# tyrmt.net
KiCad netlist of a schematic drawn in EAGLE
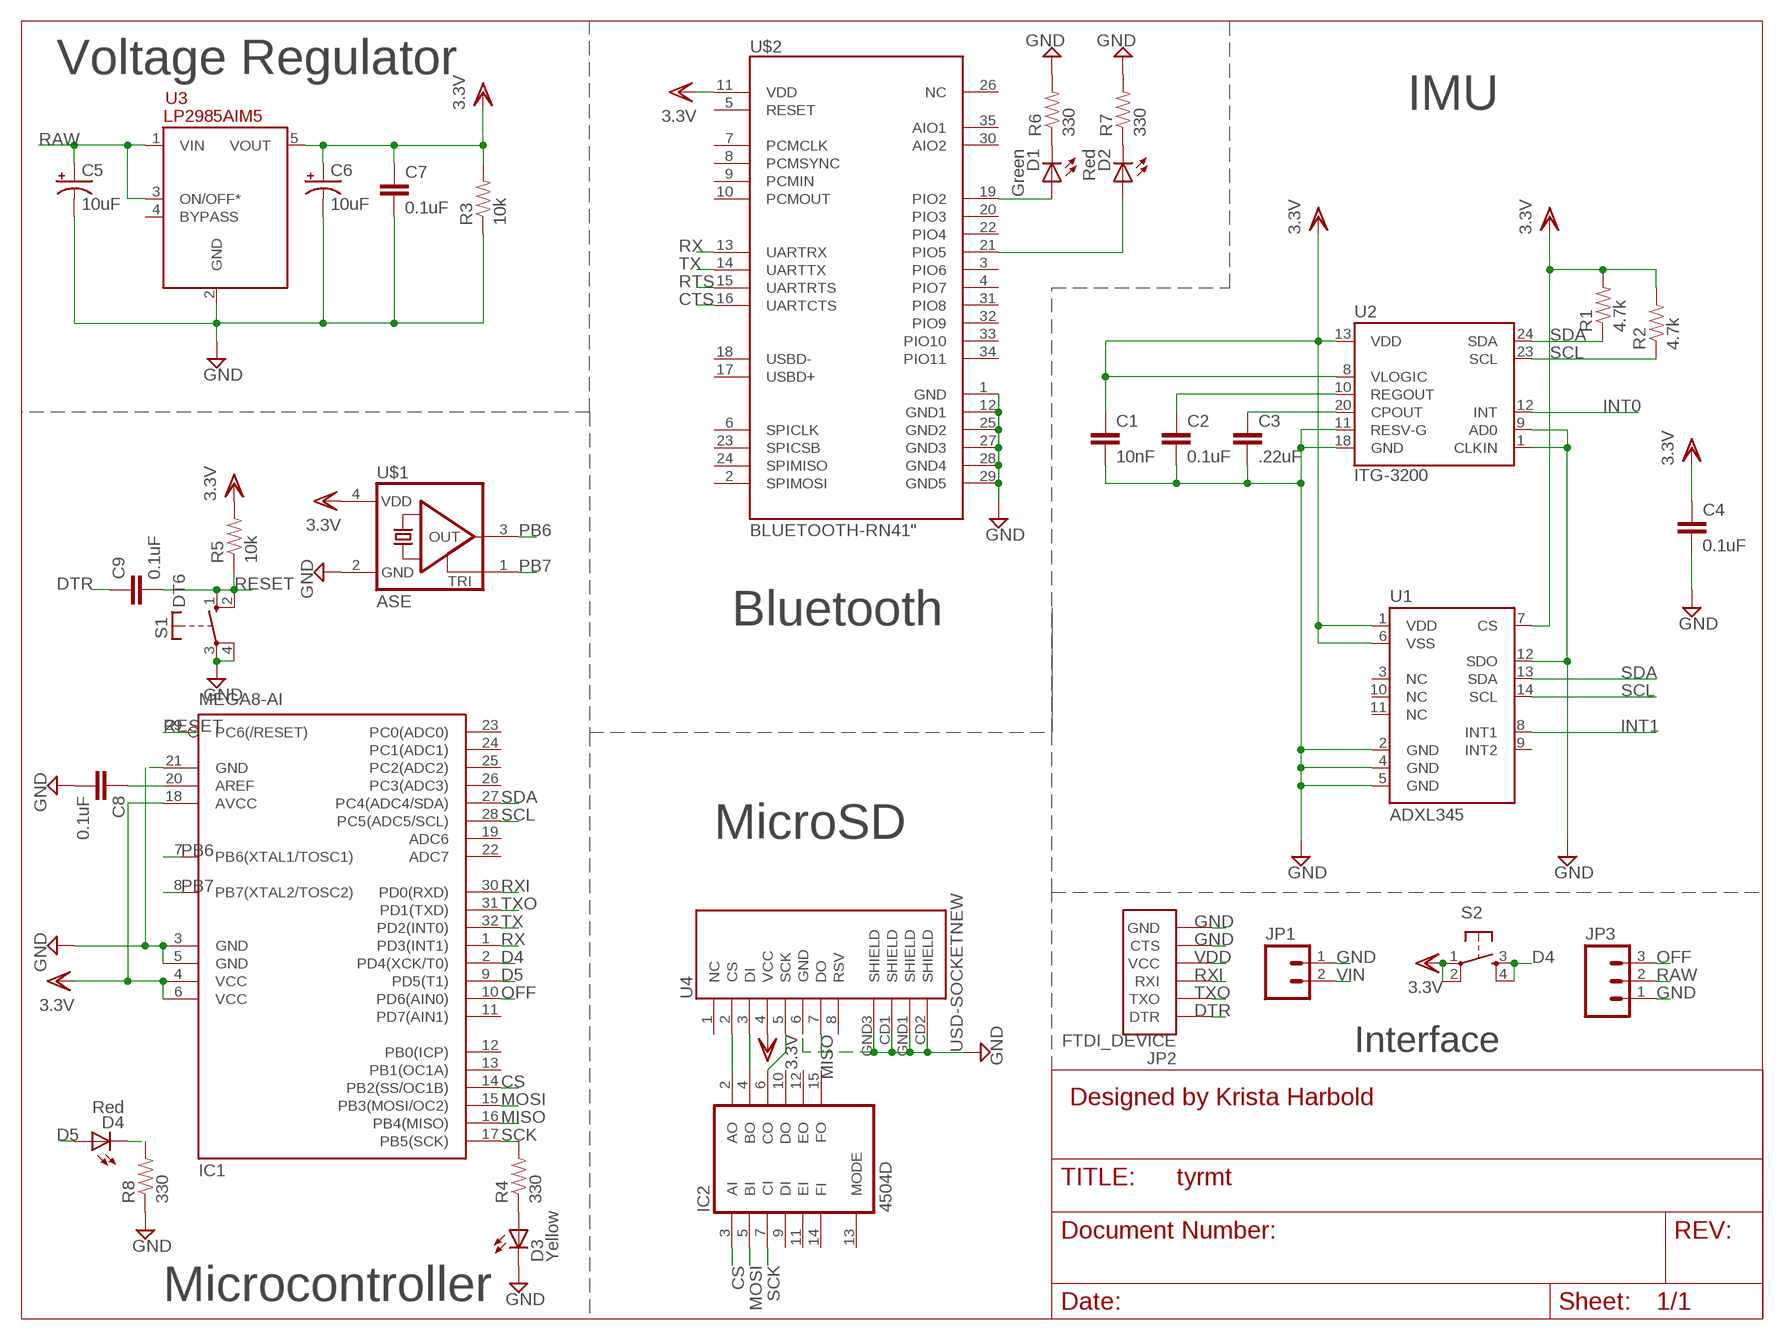
[diagram p0: schematic, sheet 1]

(export (version "E")
  (design (tool "Eeschema 10.0.6"))
  (components
    (comp (ref "C1")
      (value "10nF")
      (footprint "eagle-import:0402-CAP")
      (libsource (lib "eagle-import") (part "10NF-CER"))
    )
    (comp (ref "C2")
      (value "0.1uF")
      (footprint "eagle-import:0402-CAP")
      (libsource (lib "eagle-import") (part ".1UF-CER"))
    )
    (comp (ref "C3")
      (value ".22uF")
      (footprint "eagle-import:0402-CAP")
      (libsource (lib "eagle-import") (part ".22UF-CER"))
    )
    (comp (ref "C4")
      (value "0.1uF")
      (footprint "eagle-import:0402-CAP")
      (libsource (lib "eagle-import") (part ".1UF-CER"))
    )
    (comp (ref "C5")
      (value "10uF")
      (footprint "eagle-import:EIA3216")
      (libsource (lib "eagle-import") (part "10UF-16V-10%(TANT)"))
    )
    (comp (ref "C6")
      (value "10uF")
      (footprint "eagle-import:EIA3216")
      (libsource (lib "eagle-import") (part "10UF-16V-10%(TANT)"))
    )
    (comp (ref "C7")
      (value "0.1uF")
      (footprint "eagle-import:0402-CAP")
      (libsource (lib "eagle-import") (part ".1UF-CER"))
    )
    (comp (ref "C8")
      (value "0.1uF")
      (footprint "eagle-import:0402-CAP")
      (libsource (lib "eagle-import") (part ".1UF-CER"))
    )
    (comp (ref "C9")
      (value "0.1uF")
      (footprint "eagle-import:0402-CAP")
      (libsource (lib "eagle-import") (part ".1UF-CER"))
    )
    (comp (ref "D1")
      (value "Green")
      (footprint "eagle-import:SFH482")
      (libsource (lib "eagle-import") (part "SFH482"))
    )
    (comp (ref "D2")
      (value "Red")
      (footprint "eagle-import:SFH482")
      (libsource (lib "eagle-import") (part "SFH482"))
    )
    (comp (ref "D3")
      (value "Yellow")
      (footprint "eagle-import:SFH482")
      (libsource (lib "eagle-import") (part "SFH482"))
    )
    (comp (ref "D4")
      (value "Red")
      (footprint "eagle-import:SFH482")
      (libsource (lib "eagle-import") (part "SFH482"))
    )
    (comp (ref "IC1")
      (value "MEGA8-AI")
      (footprint "eagle-import:TQFP32-08")
      (fields (field (name "MPN") "ATMEGA8-16AU"))
      (libsource (lib "eagle-import") (part "MEGA8-AI"))
    )
    (comp (ref "IC2")
      (value "4504D")
      (footprint "eagle-import:SO16")
      (libsource (lib "eagle-import") (part "4504D"))
    )
    (comp (ref "JP1")
      (value "M02-JST-2MM-SMT")
      (footprint "eagle-import:JST-2-SMD")
      (libsource (lib "eagle-import") (part "M02-JST-2MM-SMT"))
    )
    (comp (ref "JP2")
      (value "FTDI_DEVICE")
      (footprint "eagle-import:FTDI_DEVICE_SIDE")
      (libsource (lib "eagle-import") (part "FTDI_DEVICE"))
    )
    (comp (ref "JP3")
      (value "M03POLAR")
      (footprint "eagle-import:MOLEX-1X3")
      (libsource (lib "eagle-import") (part "M03POLAR"))
    )
    (comp (ref "R1")
      (value "4.7k")
      (footprint "eagle-import:0402-RES")
      (libsource (lib "eagle-import") (part "RESISTOR0402-RES"))
    )
    (comp (ref "R2")
      (value "4.7k")
      (footprint "eagle-import:0402-RES")
      (libsource (lib "eagle-import") (part "RESISTOR0402-RES"))
    )
    (comp (ref "R3")
      (value "10k")
      (footprint "eagle-import:0402-RES")
      (libsource (lib "eagle-import") (part "RESISTOR0402-RES"))
    )
    (comp (ref "R4")
      (value "330")
      (footprint "eagle-import:0402-RES")
      (libsource (lib "eagle-import") (part "RESISTOR0402-RES"))
    )
    (comp (ref "R5")
      (value "10k")
      (footprint "eagle-import:0402-RES")
      (libsource (lib "eagle-import") (part "RESISTOR0402-RES"))
    )
    (comp (ref "R6")
      (value "330")
      (footprint "eagle-import:0402-RES")
      (libsource (lib "eagle-import") (part "RESISTOR0402-RES"))
    )
    (comp (ref "R7")
      (value "330")
      (footprint "eagle-import:0402-RES")
      (libsource (lib "eagle-import") (part "RESISTOR0402-RES"))
    )
    (comp (ref "R8")
      (value "330")
      (footprint "eagle-import:0402-RES")
      (libsource (lib "eagle-import") (part "RESISTOR0402-RES"))
    )
    (comp (ref "S1")
      (value "DT6")
      (footprint "eagle-import:DT6")
      (libsource (lib "eagle-import") (part "DT6"))
    )
    (comp (ref "S2")
      (value "TAC_SWITCHSMD")
      (footprint "eagle-import:TACTILE_SWITCH_SMD")
      (libsource (lib "eagle-import") (part "TAC_SWITCHSMD"))
    )
    (comp (ref "U$1")
      (value "ASE")
      (footprint "eagle-import:ASE")
      (libsource (lib "eagle-import") (part "ASE"))
    )
    (comp (ref "U$2")
      (value "BLUETOOTH-RN41\"")
      (footprint "eagle-import:RN41")
      (libsource (lib "eagle-import") (part "BLUETOOTH-RN41{dblquote}"))
    )
    (comp (ref "U1")
      (value "ADXL345")
      (footprint "eagle-import:LGA14")
      (libsource (lib "eagle-import") (part "ADXL345"))
    )
    (comp (ref "U2")
      (value "ITG-3200")
      (footprint "eagle-import:QFN-24")
      (libsource (lib "eagle-import") (part "ITG-3200"))
    )
    (comp (ref "U3")
      (value "LP2985AIM5")
      (footprint "eagle-import:SOT23-5L")
      (libsource (lib "eagle-import") (part "LP2985AIM5"))
    )
    (comp (ref "U4")
      (value "USD-SOCKETNEW")
      (footprint "eagle-import:MICRO-SD-SOCKET-PP")
      (libsource (lib "eagle-import") (part "USD-SOCKETNEW"))
    )
  )
  (nets
    (net (code "1") (name "/CS") (class "Default")
      (node (ref "IC1") (pin "14") (pinfunction "PB2(SS/OC1B)_14") (pintype "bidirectional"))
      (node (ref "IC2") (pin "3") (pinfunction "AI_3") (pintype "input"))
    )
    (net (code "2") (name "/CTS") (class "Default")
      (node (ref "U$2") (pin "16") (pinfunction "UARTCTS_16") (pintype "bidirectional"))
    )
    (net (code "3") (name "/D4") (class "Default")
      (node (ref "IC1") (pin "2") (pinfunction "PD4(XCK/T0)_2") (pintype "bidirectional"))
      (node (ref "S2") (pin "3") (pinfunction "3_3") (pintype "passive"))
      (node (ref "S2") (pin "4") (pinfunction "4_4") (pintype "passive"))
    )
    (net (code "4") (name "/D5") (class "Default")
      (node (ref "D4") (pin "A") (pinfunction "A_A") (pintype "passive"))
      (node (ref "IC1") (pin "9") (pinfunction "PD5(T1)_9") (pintype "bidirectional"))
    )
    (net (code "5") (name "/DTR") (class "Default")
      (node (ref "C9") (pin "1") (pinfunction "1_1") (pintype "passive"))
      (node (ref "JP2") (pin "P$1") (pinfunction "DTR_P$1") (pintype "bidirectional"))
    )
    (net (code "6") (name "/INT0") (class "Default")
      (node (ref "U2") (pin "12") (pinfunction "INT_12") (pintype "bidirectional"))
    )
    (net (code "7") (name "/INT1") (class "Default")
      (node (ref "U1") (pin "8") (pinfunction "INT1_8") (pintype "bidirectional"))
    )
    (net (code "8") (name "/MISO") (class "Default")
      (node (ref "IC1") (pin "16") (pinfunction "PB4(MISO)_16") (pintype "bidirectional"))
      (node (ref "U4") (pin "7") (pinfunction "DO_7") (pintype "bidirectional"))
    )
    (net (code "9") (name "/MOSI") (class "Default")
      (node (ref "IC1") (pin "15") (pinfunction "PB3(MOSI/OC2)_15") (pintype "bidirectional"))
      (node (ref "IC2") (pin "5") (pinfunction "BI_5") (pintype "input"))
    )
    (net (code "10") (name "/OFF") (class "Default")
      (node (ref "IC1") (pin "10") (pinfunction "PD6(AIN0)_10") (pintype "bidirectional"))
      (node (ref "JP3") (pin "3") (pinfunction "3_3") (pintype "passive"))
    )
    (net (code "11") (name "/PB6") (class "Default")
      (node (ref "IC1") (pin "7") (pinfunction "PB6(XTAL1/TOSC1)_7") (pintype "bidirectional"))
      (node (ref "U$1") (pin "3") (pinfunction "OUT_3") (pintype "output"))
    )
    (net (code "12") (name "/PB7") (class "Default")
      (node (ref "IC1") (pin "8") (pinfunction "PB7(XTAL2/TOSC2)_8") (pintype "bidirectional"))
      (node (ref "U$1") (pin "1") (pinfunction "TRI_1") (pintype "input"))
    )
    (net (code "13") (name "/RAW") (class "Default")
      (node (ref "C5") (pin "A") (pinfunction "+_A") (pintype "passive"))
      (node (ref "JP3") (pin "2") (pinfunction "2_2") (pintype "passive"))
      (node (ref "U3") (pin "1") (pinfunction "VIN_1") (pintype "passive"))
      (node (ref "U3") (pin "3") (pinfunction "ON/OFF*_3") (pintype "passive"))
    )
    (net (code "14") (name "/RESET") (class "Default")
      (node (ref "C9") (pin "2") (pinfunction "2_2") (pintype "passive"))
      (node (ref "IC1") (pin "29") (pinfunction "PC6(/RESET)_29") (pintype "bidirectional"))
      (node (ref "R5") (pin "1") (pinfunction "1_1") (pintype "passive"))
      (node (ref "S1") (pin "1") (pinfunction "S_1") (pintype "passive"))
      (node (ref "S1") (pin "2") (pinfunction "S_2") (pintype "passive"))
    )
    (net (code "15") (name "/RTS") (class "Default")
      (node (ref "U$2") (pin "15") (pinfunction "UARTRTS_15") (pintype "bidirectional"))
    )
    (net (code "16") (name "/RX") (class "Default")
      (node (ref "IC1") (pin "1") (pinfunction "PD3(INT1)_1") (pintype "bidirectional"))
      (node (ref "U$2") (pin "13") (pinfunction "UARTRX_13") (pintype "bidirectional"))
    )
    (net (code "17") (name "/RXI") (class "Default")
      (node (ref "IC1") (pin "30") (pinfunction "PD0(RXD)_30") (pintype "bidirectional"))
      (node (ref "JP2") (pin "P$3") (pinfunction "RXI_P$3") (pintype "bidirectional"))
    )
    (net (code "18") (name "/SCK") (class "Default")
      (node (ref "IC1") (pin "17") (pinfunction "PB5(SCK)_17") (pintype "bidirectional"))
      (node (ref "IC2") (pin "7") (pinfunction "CI_7") (pintype "input"))
      (node (ref "R4") (pin "2") (pinfunction "2_2") (pintype "passive"))
    )
    (net (code "19") (name "/SCL") (class "Default")
      (node (ref "IC1") (pin "28") (pinfunction "PC5(ADC5/SCL)_28") (pintype "bidirectional"))
      (node (ref "R2") (pin "1") (pinfunction "1_1") (pintype "passive"))
      (node (ref "U1") (pin "14") (pinfunction "SCL_14") (pintype "bidirectional"))
      (node (ref "U2") (pin "23") (pinfunction "SCL_23") (pintype "bidirectional"))
    )
    (net (code "20") (name "/SDA") (class "Default")
      (node (ref "IC1") (pin "27") (pinfunction "PC4(ADC4/SDA)_27") (pintype "bidirectional"))
      (node (ref "R1") (pin "1") (pinfunction "1_1") (pintype "passive"))
      (node (ref "U1") (pin "13") (pinfunction "SDA_13") (pintype "bidirectional"))
      (node (ref "U2") (pin "24") (pinfunction "SDA_24") (pintype "bidirectional"))
    )
    (net (code "21") (name "/TX") (class "Default")
      (node (ref "IC1") (pin "32") (pinfunction "PD2(INT0)_32") (pintype "bidirectional"))
      (node (ref "U$2") (pin "14") (pinfunction "UARTTX_14") (pintype "bidirectional"))
    )
    (net (code "22") (name "/TXO") (class "Default")
      (node (ref "IC1") (pin "31") (pinfunction "PD1(TXD)_31") (pintype "bidirectional"))
      (node (ref "JP2") (pin "P$2") (pinfunction "TXO_P$2") (pintype "bidirectional"))
    )
    (net (code "23") (name "/VIN") (class "Default")
      (node (ref "JP1") (pin "2") (pinfunction "1_2") (pintype "passive"))
    )
    (net (code "24") (name "3.3V") (class "Default")
      (node (ref "C1") (pin "1") (pinfunction "1_1") (pintype "passive"))
      (node (ref "C4") (pin "1") (pinfunction "1_1") (pintype "passive"))
      (node (ref "C6") (pin "A") (pinfunction "+_A") (pintype "passive"))
      (node (ref "C7") (pin "1") (pinfunction "1_1") (pintype "passive"))
      (node (ref "IC1") (pin "18") (pinfunction "AVCC_18") (pintype "power_in"))
      (node (ref "IC1") (pin "4") (pinfunction "VCC_4") (pintype "power_in"))
      (node (ref "IC1") (pin "6") (pinfunction "VCC_6") (pintype "power_in"))
      (node (ref "JP2") (pin "P$4") (pinfunction "VCC_P$4") (pintype "bidirectional"))
      (node (ref "R1") (pin "2") (pinfunction "2_2") (pintype "passive"))
      (node (ref "R2") (pin "2") (pinfunction "2_2") (pintype "passive"))
      (node (ref "R3") (pin "2") (pinfunction "2_2") (pintype "passive"))
      (node (ref "R5") (pin "2") (pinfunction "2_2") (pintype "passive"))
      (node (ref "S2") (pin "1") (pinfunction "1_1") (pintype "passive"))
      (node (ref "S2") (pin "2") (pinfunction "2_2") (pintype "passive"))
      (node (ref "U$1") (pin "4") (pinfunction "VDD_4") (pintype "power_in"))
      (node (ref "U$2") (pin "11") (pinfunction "VDD_11") (pintype "bidirectional"))
      (node (ref "U1") (pin "1") (pinfunction "VDD_1") (pintype "bidirectional"))
      (node (ref "U1") (pin "6") (pinfunction "VSS_6") (pintype "bidirectional"))
      (node (ref "U1") (pin "7") (pinfunction "CS_7") (pintype "bidirectional"))
      (node (ref "U2") (pin "13") (pinfunction "VDD_13") (pintype "bidirectional"))
      (node (ref "U2") (pin "8") (pinfunction "VLOGIC_8") (pintype "bidirectional"))
      (node (ref "U3") (pin "5") (pinfunction "VOUT_5") (pintype "passive"))
      (node (ref "U4") (pin "4") (pinfunction "VCC_4") (pintype "bidirectional"))
    )
    (net (code "25") (name "GND") (class "Default")
      (node (ref "C1") (pin "2") (pinfunction "2_2") (pintype "passive"))
      (node (ref "C2") (pin "2") (pinfunction "2_2") (pintype "passive"))
      (node (ref "C3") (pin "2") (pinfunction "2_2") (pintype "passive"))
      (node (ref "C4") (pin "2") (pinfunction "2_2") (pintype "passive"))
      (node (ref "C5") (pin "C") (pinfunction "-_C") (pintype "passive"))
      (node (ref "C6") (pin "C") (pinfunction "-_C") (pintype "passive"))
      (node (ref "C7") (pin "2") (pinfunction "2_2") (pintype "passive"))
      (node (ref "C8") (pin "2") (pinfunction "2_2") (pintype "passive"))
      (node (ref "D3") (pin "K") (pinfunction "C_K") (pintype "passive"))
      (node (ref "IC1") (pin "21") (pinfunction "GND_21") (pintype "power_in"))
      (node (ref "IC1") (pin "3") (pinfunction "GND_3") (pintype "power_in"))
      (node (ref "IC1") (pin "5") (pinfunction "GND_5") (pintype "power_in"))
      (node (ref "JP1") (pin "1") (pinfunction "2_1") (pintype "passive"))
      (node (ref "JP2") (pin "P$5") (pinfunction "CTS_P$5") (pintype "bidirectional"))
      (node (ref "JP2") (pin "P$6") (pinfunction "GND_P$6") (pintype "bidirectional"))
      (node (ref "JP3") (pin "1") (pinfunction "1_1") (pintype "passive"))
      (node (ref "R3") (pin "1") (pinfunction "1_1") (pintype "passive"))
      (node (ref "R6") (pin "2") (pinfunction "2_2") (pintype "passive"))
      (node (ref "R7") (pin "2") (pinfunction "2_2") (pintype "passive"))
      (node (ref "R8") (pin "1") (pinfunction "1_1") (pintype "passive"))
      (node (ref "S1") (pin "3") (pinfunction "P_3") (pintype "passive"))
      (node (ref "S1") (pin "4") (pinfunction "P_4") (pintype "passive"))
      (node (ref "U$1") (pin "2") (pinfunction "GND_2") (pintype "power_in"))
      (node (ref "U$2") (pin "1") (pinfunction "GND_1") (pintype "bidirectional"))
      (node (ref "U$2") (pin "12") (pinfunction "GND1_12") (pintype "bidirectional"))
      (node (ref "U$2") (pin "25") (pinfunction "GND2_25") (pintype "bidirectional"))
      (node (ref "U$2") (pin "27") (pinfunction "GND3_27") (pintype "bidirectional"))
      (node (ref "U$2") (pin "28") (pinfunction "GND4_28") (pintype "bidirectional"))
      (node (ref "U$2") (pin "29") (pinfunction "GND5_29") (pintype "bidirectional"))
      (node (ref "U1") (pin "12") (pinfunction "SDO_12") (pintype "bidirectional"))
      (node (ref "U1") (pin "2") (pinfunction "GND_2") (pintype "bidirectional"))
      (node (ref "U1") (pin "4") (pinfunction "GND_4") (pintype "bidirectional"))
      (node (ref "U1") (pin "5") (pinfunction "GND_5") (pintype "bidirectional"))
      (node (ref "U2") (pin "1") (pinfunction "CLKIN_1") (pintype "bidirectional"))
      (node (ref "U2") (pin "11") (pinfunction "RESV-G_11") (pintype "bidirectional"))
      (node (ref "U2") (pin "18") (pinfunction "GND_18") (pintype "bidirectional"))
      (node (ref "U2") (pin "9") (pinfunction "AD0_9") (pintype "bidirectional"))
      (node (ref "U3") (pin "2") (pinfunction "GND_2") (pintype "passive"))
      (node (ref "U4") (pin "6") (pinfunction "GND_6") (pintype "bidirectional"))
      (node (ref "U4") (pin "CD1") (pinfunction "SHIELD_CD1") (pintype "bidirectional"))
      (node (ref "U4") (pin "CD2") (pinfunction "SHIELD_CD2") (pintype "bidirectional"))
      (node (ref "U4") (pin "GND1") (pinfunction "SHIELD_GND1") (pintype "bidirectional"))
      (node (ref "U4") (pin "GND3") (pinfunction "SHIELD_GND3") (pintype "bidirectional"))
    )
    (net (code "26") (name "Net-(D1-C)") (class "Default")
      (node (ref "D1") (pin "K") (pinfunction "C_K") (pintype "passive"))
      (node (ref "R6") (pin "1") (pinfunction "1_1") (pintype "passive"))
    )
    (net (code "27") (name "Net-(D2-C)") (class "Default")
      (node (ref "D2") (pin "K") (pinfunction "C_K") (pintype "passive"))
      (node (ref "R7") (pin "1") (pinfunction "1_1") (pintype "passive"))
    )
    (net (code "28") (name "Net-(D3-PadA)") (class "Default")
      (node (ref "D3") (pin "A") (pinfunction "A_A") (pintype "passive"))
      (node (ref "R4") (pin "1") (pinfunction "1_1") (pintype "passive"))
    )
    (net (code "29") (name "Net-(D4-C)") (class "Default")
      (node (ref "D4") (pin "K") (pinfunction "C_K") (pintype "passive"))
      (node (ref "R8") (pin "2") (pinfunction "2_2") (pintype "passive"))
    )
    (net (code "30") (name "Net-(IC1-AREF)") (class "Default")
      (node (ref "C8") (pin "1") (pinfunction "1_1") (pintype "passive"))
      (node (ref "IC1") (pin "20") (pinfunction "AREF_20") (pintype "passive"))
    )
    (net (code "31") (name "Net-(IC2A-AO)") (class "Default")
      (node (ref "IC2") (pin "2") (pinfunction "AO_2") (pintype "output"))
      (node (ref "U4") (pin "2") (pinfunction "CS_2") (pintype "bidirectional"))
    )
    (net (code "32") (name "Net-(IC2A-BO)") (class "Default")
      (node (ref "IC2") (pin "4") (pinfunction "BO_4") (pintype "output"))
      (node (ref "U4") (pin "3") (pinfunction "DI_3") (pintype "bidirectional"))
    )
    (net (code "33") (name "Net-(IC2A-CO)") (class "Default")
      (node (ref "IC2") (pin "6") (pinfunction "CO_6") (pintype "output"))
      (node (ref "U4") (pin "5") (pinfunction "SCK_5") (pintype "bidirectional"))
    )
    (net (code "34") (name "Net-(U$2-PIO2)") (class "Default")
      (node (ref "D1") (pin "A") (pinfunction "A_A") (pintype "passive"))
      (node (ref "U$2") (pin "19") (pinfunction "PIO2_19") (pintype "bidirectional"))
    )
    (net (code "35") (name "Net-(U$2-PIO5)") (class "Default")
      (node (ref "D2") (pin "A") (pinfunction "A_A") (pintype "passive"))
      (node (ref "U$2") (pin "21") (pinfunction "PIO5_21") (pintype "bidirectional"))
    )
    (net (code "36") (name "Net-(U2-CPOUT)") (class "Default")
      (node (ref "C3") (pin "1") (pinfunction "1_1") (pintype "passive"))
      (node (ref "U2") (pin "20") (pinfunction "CPOUT_20") (pintype "bidirectional"))
    )
    (net (code "37") (name "Net-(U2-REGOUT)") (class "Default")
      (node (ref "C2") (pin "1") (pinfunction "1_1") (pintype "passive"))
      (node (ref "U2") (pin "10") (pinfunction "REGOUT_10") (pintype "bidirectional"))
    )
    (net (code "38") (name "unconnected-(IC1-ADC6-Pad19)") (class "Default")
      (node (ref "IC1") (pin "19") (pinfunction "ADC6_19") (pintype "bidirectional"))
    )
    (net (code "39") (name "unconnected-(IC1-ADC7-Pad22)") (class "Default")
      (node (ref "IC1") (pin "22") (pinfunction "ADC7_22") (pintype "bidirectional"))
    )
    (net (code "40") (name "unconnected-(IC1-PB0(ICP)-Pad12)") (class "Default")
      (node (ref "IC1") (pin "12") (pinfunction "PB0(ICP)_12") (pintype "bidirectional"))
    )
    (net (code "41") (name "unconnected-(IC1-PB1(OC1A)-Pad13)") (class "Default")
      (node (ref "IC1") (pin "13") (pinfunction "PB1(OC1A)_13") (pintype "bidirectional"))
    )
    (net (code "42") (name "unconnected-(IC1-PC0(ADC0)-Pad23)") (class "Default")
      (node (ref "IC1") (pin "23") (pinfunction "PC0(ADC0)_23") (pintype "bidirectional"))
    )
    (net (code "43") (name "unconnected-(IC1-PC1(ADC1)-Pad24)") (class "Default")
      (node (ref "IC1") (pin "24") (pinfunction "PC1(ADC1)_24") (pintype "bidirectional"))
    )
    (net (code "44") (name "unconnected-(IC1-PC2(ADC2)-Pad25)") (class "Default")
      (node (ref "IC1") (pin "25") (pinfunction "PC2(ADC2)_25") (pintype "bidirectional"))
    )
    (net (code "45") (name "unconnected-(IC1-PC3(ADC3)-Pad26)") (class "Default")
      (node (ref "IC1") (pin "26") (pinfunction "PC3(ADC3)_26") (pintype "bidirectional"))
    )
    (net (code "46") (name "unconnected-(IC1-PD7(AIN1)-Pad11)") (class "Default")
      (node (ref "IC1") (pin "11") (pinfunction "PD7(AIN1)_11") (pintype "bidirectional"))
    )
    (net (code "47") (name "unconnected-(IC2A-DI-Pad9)") (class "Default")
      (node (ref "IC2") (pin "9") (pinfunction "DI_9") (pintype "input"))
    )
    (net (code "48") (name "unconnected-(IC2A-DO-Pad10)") (class "Default")
      (node (ref "IC2") (pin "10") (pinfunction "DO_10") (pintype "output"))
    )
    (net (code "49") (name "unconnected-(IC2A-EI-Pad11)") (class "Default")
      (node (ref "IC2") (pin "11") (pinfunction "EI_11") (pintype "input"))
    )
    (net (code "50") (name "unconnected-(IC2A-EO-Pad12)") (class "Default")
      (node (ref "IC2") (pin "12") (pinfunction "EO_12") (pintype "output"))
    )
    (net (code "51") (name "unconnected-(IC2A-FI-Pad14)") (class "Default")
      (node (ref "IC2") (pin "14") (pinfunction "FI_14") (pintype "input"))
    )
    (net (code "52") (name "unconnected-(IC2A-FO-Pad15)") (class "Default")
      (node (ref "IC2") (pin "15") (pinfunction "FO_15") (pintype "output"))
    )
    (net (code "53") (name "unconnected-(IC2A-MODE-Pad13)") (class "Default")
      (node (ref "IC2") (pin "13") (pinfunction "MODE_13") (pintype "input"))
    )
    (net (code "54") (name "unconnected-(U$2-AIO1-Pad35)") (class "Default")
      (node (ref "U$2") (pin "35") (pinfunction "AIO1_35") (pintype "bidirectional"))
    )
    (net (code "55") (name "unconnected-(U$2-AIO2-Pad30)") (class "Default")
      (node (ref "U$2") (pin "30") (pinfunction "AIO2_30") (pintype "bidirectional"))
    )
    (net (code "56") (name "unconnected-(U$2-NC-Pad26)") (class "Default")
      (node (ref "U$2") (pin "26") (pinfunction "NC_26") (pintype "bidirectional"))
    )
    (net (code "57") (name "unconnected-(U$2-PCMCLK-Pad7)") (class "Default")
      (node (ref "U$2") (pin "7") (pinfunction "PCMCLK_7") (pintype "bidirectional"))
    )
    (net (code "58") (name "unconnected-(U$2-PCMIN-Pad9)") (class "Default")
      (node (ref "U$2") (pin "9") (pinfunction "PCMIN_9") (pintype "bidirectional"))
    )
    (net (code "59") (name "unconnected-(U$2-PCMOUT-Pad10)") (class "Default")
      (node (ref "U$2") (pin "10") (pinfunction "PCMOUT_10") (pintype "bidirectional"))
    )
    (net (code "60") (name "unconnected-(U$2-PCMSYNC-Pad8)") (class "Default")
      (node (ref "U$2") (pin "8") (pinfunction "PCMSYNC_8") (pintype "bidirectional"))
    )
    (net (code "61") (name "unconnected-(U$2-PIO3-Pad20)") (class "Default")
      (node (ref "U$2") (pin "20") (pinfunction "PIO3_20") (pintype "bidirectional"))
    )
    (net (code "62") (name "unconnected-(U$2-PIO4-Pad22)") (class "Default")
      (node (ref "U$2") (pin "22") (pinfunction "PIO4_22") (pintype "bidirectional"))
    )
    (net (code "63") (name "unconnected-(U$2-PIO6-Pad3)") (class "Default")
      (node (ref "U$2") (pin "3") (pinfunction "PIO6_3") (pintype "bidirectional"))
    )
    (net (code "64") (name "unconnected-(U$2-PIO7-Pad4)") (class "Default")
      (node (ref "U$2") (pin "4") (pinfunction "PIO7_4") (pintype "bidirectional"))
    )
    (net (code "65") (name "unconnected-(U$2-PIO8-Pad31)") (class "Default")
      (node (ref "U$2") (pin "31") (pinfunction "PIO8_31") (pintype "bidirectional"))
    )
    (net (code "66") (name "unconnected-(U$2-PIO9-Pad32)") (class "Default")
      (node (ref "U$2") (pin "32") (pinfunction "PIO9_32") (pintype "bidirectional"))
    )
    (net (code "67") (name "unconnected-(U$2-PIO10-Pad33)") (class "Default")
      (node (ref "U$2") (pin "33") (pinfunction "PIO10_33") (pintype "bidirectional"))
    )
    (net (code "68") (name "unconnected-(U$2-PIO11-Pad34)") (class "Default")
      (node (ref "U$2") (pin "34") (pinfunction "PIO11_34") (pintype "bidirectional"))
    )
    (net (code "69") (name "unconnected-(U$2-RESET-Pad5)") (class "Default")
      (node (ref "U$2") (pin "5") (pinfunction "RESET_5") (pintype "bidirectional"))
    )
    (net (code "70") (name "unconnected-(U$2-SPICLK-Pad6)") (class "Default")
      (node (ref "U$2") (pin "6") (pinfunction "SPICLK_6") (pintype "bidirectional"))
    )
    (net (code "71") (name "unconnected-(U$2-SPICSB-Pad23)") (class "Default")
      (node (ref "U$2") (pin "23") (pinfunction "SPICSB_23") (pintype "bidirectional"))
    )
    (net (code "72") (name "unconnected-(U$2-SPIMISO-Pad24)") (class "Default")
      (node (ref "U$2") (pin "24") (pinfunction "SPIMISO_24") (pintype "bidirectional"))
    )
    (net (code "73") (name "unconnected-(U$2-SPIMOSI-Pad2)") (class "Default")
      (node (ref "U$2") (pin "2") (pinfunction "SPIMOSI_2") (pintype "bidirectional"))
    )
    (net (code "74") (name "unconnected-(U$2-USBD+-Pad17)") (class "Default")
      (node (ref "U$2") (pin "17") (pinfunction "USBD+_17") (pintype "bidirectional"))
    )
    (net (code "75") (name "unconnected-(U$2-USBD--Pad18)") (class "Default")
      (node (ref "U$2") (pin "18") (pinfunction "USBD-_18") (pintype "bidirectional"))
    )
    (net (code "76") (name "unconnected-(U1-INT2-Pad9)") (class "Default")
      (node (ref "U1") (pin "9") (pinfunction "INT2_9") (pintype "bidirectional"))
    )
    (net (code "77") (name "unconnected-(U1-NC-Pad3)") (class "Default")
      (node (ref "U1") (pin "3") (pinfunction "NC_3") (pintype "bidirectional"))
    )
    (net (code "78") (name "unconnected-(U1-NC-Pad10)") (class "Default")
      (node (ref "U1") (pin "10") (pinfunction "NC_10") (pintype "bidirectional"))
    )
    (net (code "79") (name "unconnected-(U1-NC-Pad11)") (class "Default")
      (node (ref "U1") (pin "11") (pinfunction "NC_11") (pintype "bidirectional"))
    )
    (net (code "80") (name "unconnected-(U3-BYPASS-Pad4)") (class "Default")
      (node (ref "U3") (pin "4") (pinfunction "BYPASS_4") (pintype "passive"))
    )
    (net (code "81") (name "unconnected-(U4-NC-Pad1)") (class "Default")
      (node (ref "U4") (pin "1") (pinfunction "NC_1") (pintype "bidirectional"))
    )
    (net (code "82") (name "unconnected-(U4-RSV-Pad8)") (class "Default")
      (node (ref "U4") (pin "8") (pinfunction "RSV_8") (pintype "bidirectional"))
    )
  )
)
